# icom_interface.net
KiCad netlist of a schematic drawn in EAGLE
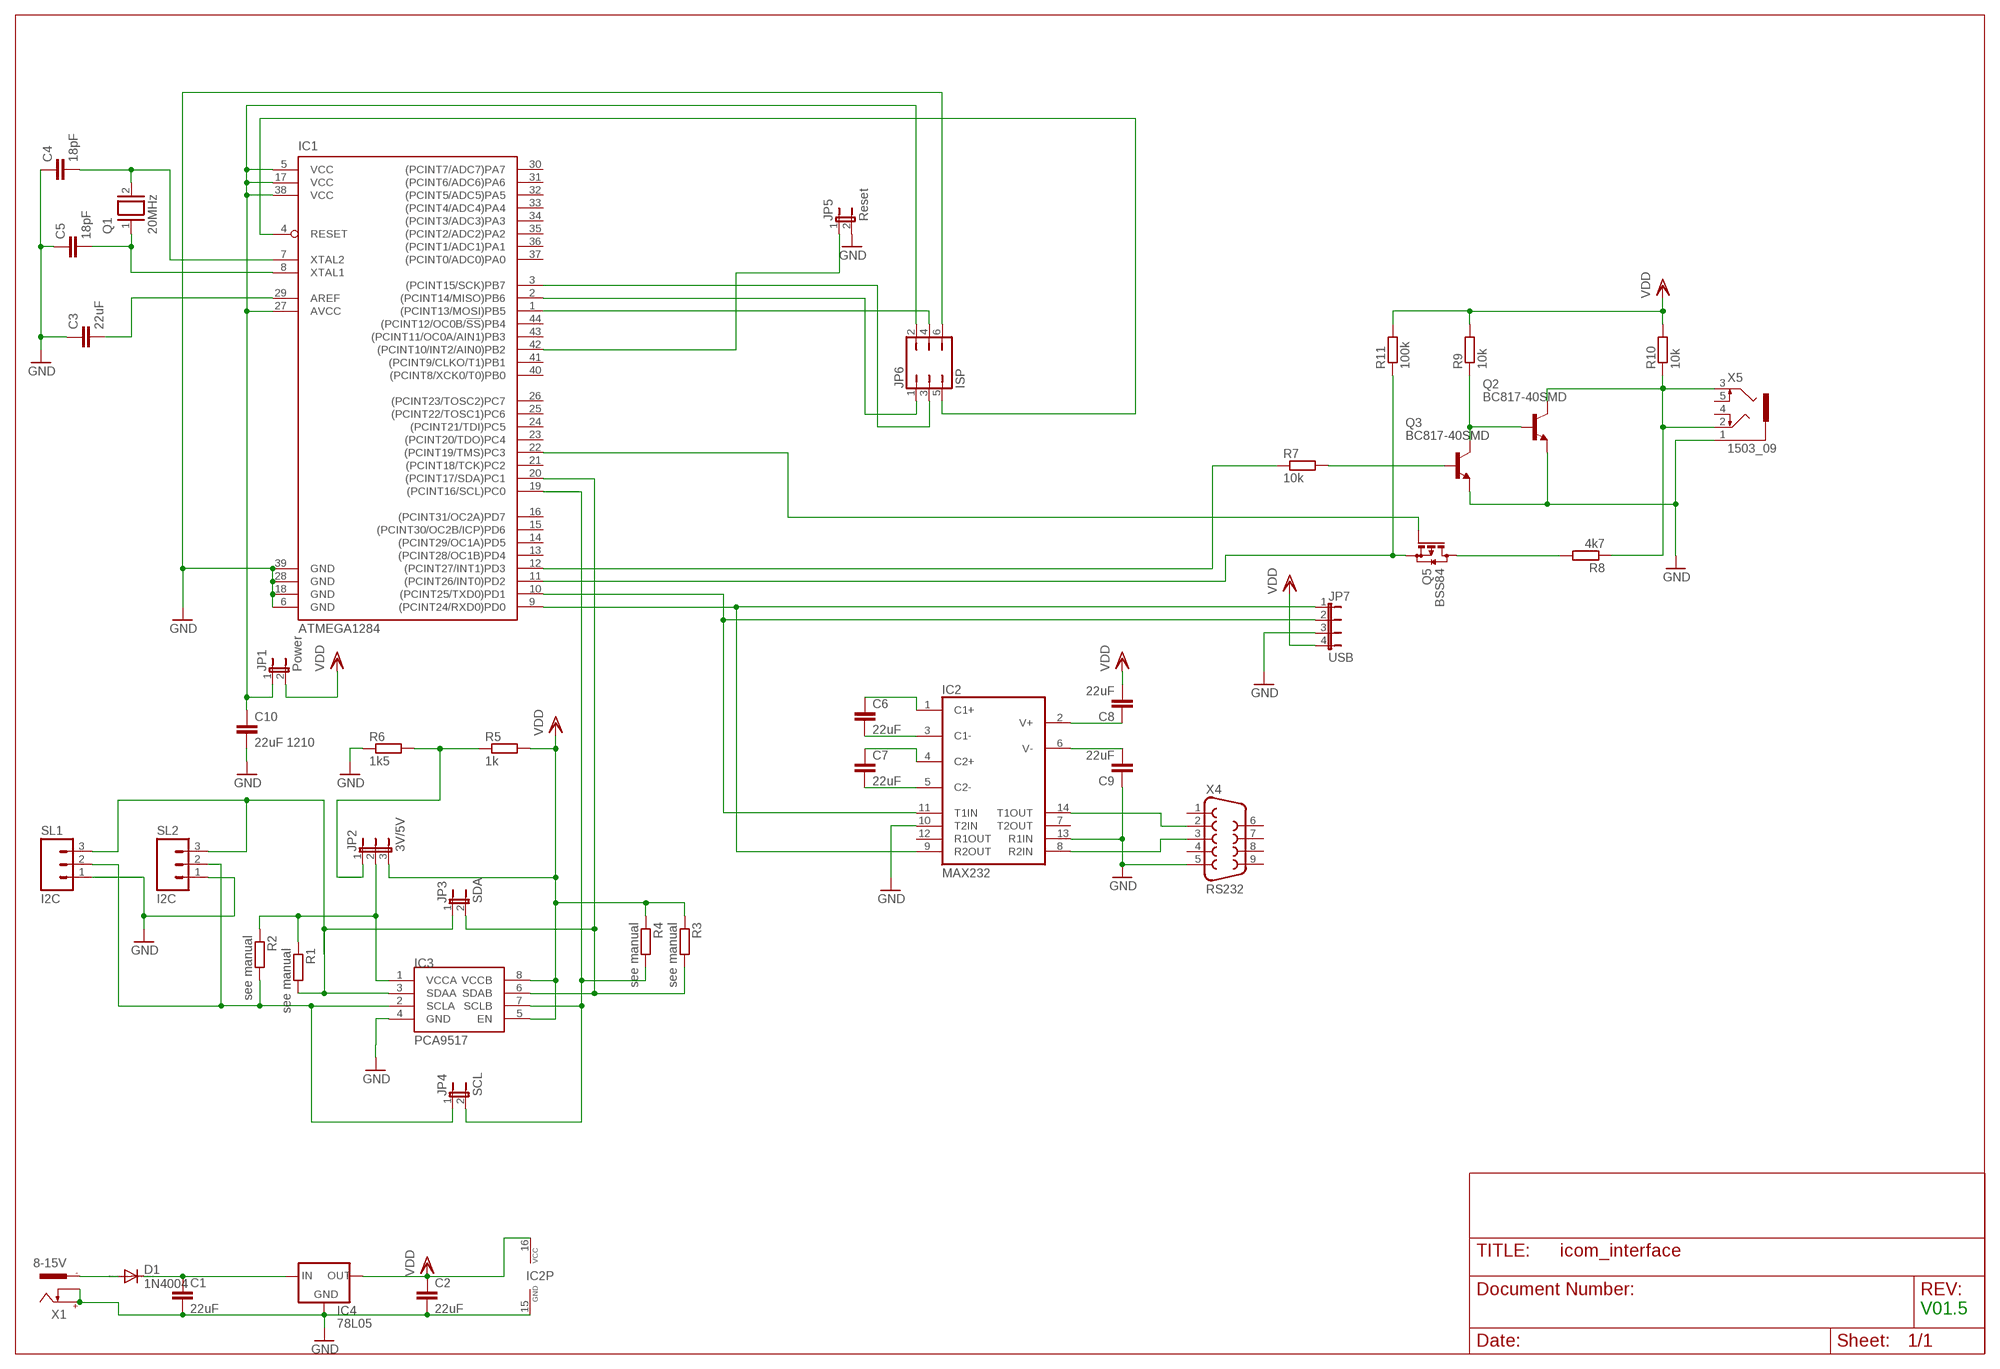
[diagram p0: schematic, sheet 1]

(export (version "E")
  (design (tool "Eeschema 10.0.6"))
  (components
    (comp (ref "C1")
      (value "22uF")
      (footprint "eagle-import:C1206")
      (libsource (lib "eagle-import") (part "C-EUC1206"))
    )
    (comp (ref "C2")
      (value "22uF")
      (footprint "eagle-import:C1206")
      (libsource (lib "eagle-import") (part "C-EUC1206"))
    )
    (comp (ref "C3")
      (value "22uF")
      (footprint "eagle-import:C1206")
      (libsource (lib "eagle-import") (part "C-EUC1206"))
    )
    (comp (ref "C4")
      (value "18pF")
      (footprint "eagle-import:C025-025X050")
      (libsource (lib "eagle-import") (part "resistor_C-EU025-025X050"))
    )
    (comp (ref "C5")
      (value "18pF")
      (footprint "eagle-import:C025-025X050")
      (libsource (lib "eagle-import") (part "resistor_C-EU025-025X050"))
    )
    (comp (ref "C6")
      (value "22uF")
      (footprint "eagle-import:C1206")
      (libsource (lib "eagle-import") (part "C-EUC1206"))
    )
    (comp (ref "C7")
      (value "22uF")
      (footprint "eagle-import:C1206")
      (libsource (lib "eagle-import") (part "C-EUC1206"))
    )
    (comp (ref "C8")
      (value "22uF")
      (footprint "eagle-import:C1206")
      (libsource (lib "eagle-import") (part "C-EUC1206"))
    )
    (comp (ref "C9")
      (value "22uF")
      (footprint "eagle-import:C1206")
      (libsource (lib "eagle-import") (part "C-EUC1206"))
    )
    (comp (ref "C10")
      (value "22uF 1210")
      (footprint "eagle-import:C1206")
      (libsource (lib "eagle-import") (part "C-EUC1206"))
    )
    (comp (ref "D1")
      (value "1N4004")
      (footprint "eagle-import:DO41-10")
      (libsource (lib "eagle-import") (part "1N4004"))
    )
    (comp (ref "IC1")
      (value "ATMEGA1284")
      (footprint "eagle-import:TQFP44")
      (fields (field (name "MPN") "ATMEGA644PV-10AU"))
      (libsource (lib "eagle-import") (part "ATMEGA644A"))
    )
    (comp (ref "IC2")
      (value "MAX232")
      (footprint "eagle-import:DIL16")
      (fields (field (name "MF") "MAXIM") (field (name "MPN") "MAX232ACPE+"))
      (libsource (lib "eagle-import") (part "MAX232"))
    )
    (comp (ref "IC3")
      (value "PCA9517")
      (footprint "eagle-import:SO-08")
      (libsource (lib "eagle-import") (part "PCA9517"))
    )
    (comp (ref "IC4")
      (value "78L05")
      (footprint "eagle-import:78LXX")
      (libsource (lib "eagle-import") (part "78LXX"))
    )
    (comp (ref "JP1")
      (value "Power")
      (footprint "eagle-import:JP1")
      (libsource (lib "eagle-import") (part "JP1E"))
    )
    (comp (ref "JP2")
      (value "3V/5V")
      (footprint "eagle-import:JP2")
      (libsource (lib "eagle-import") (part "JP2E"))
    )
    (comp (ref "JP3")
      (value "SDA")
      (footprint "eagle-import:JP1")
      (libsource (lib "eagle-import") (part "JP1E"))
    )
    (comp (ref "JP4")
      (value "SCL")
      (footprint "eagle-import:JP1")
      (libsource (lib "eagle-import") (part "JP1E"))
    )
    (comp (ref "JP5")
      (value "Reset")
      (footprint "eagle-import:JP1")
      (libsource (lib "eagle-import") (part "JP1E"))
    )
    (comp (ref "JP6")
      (value "ISP")
      (footprint "eagle-import:JP3Q")
      (libsource (lib "eagle-import") (part "JP3Q"))
    )
    (comp (ref "JP7")
      (value "USB")
      (footprint "eagle-import:JP4")
      (libsource (lib "eagle-import") (part "JP4E"))
    )
    (comp (ref "Q1")
      (value "20MHz")
      (footprint "eagle-import:QS")
      (libsource (lib "eagle-import") (part "XTAL/S"))
    )
    (comp (ref "Q2")
      (value "BC817-40SMD")
      (footprint "eagle-import:SOT23-BEC")
      (libsource (lib "eagle-import") (part "BC817SMD-40"))
    )
    (comp (ref "Q3")
      (value "BC817-40SMD")
      (footprint "eagle-import:SOT23-BEC")
      (libsource (lib "eagle-import") (part "BC817SMD-40"))
    )
    (comp (ref "Q5")
      (value "BSS84")
      (footprint "eagle-import:SOT23")
      (libsource (lib "eagle-import") (part "BSS84"))
    )
    (comp (ref "R1")
      (value "see manual")
      (footprint "eagle-import:R1206")
      (libsource (lib "eagle-import") (part "R-EU_R1206"))
    )
    (comp (ref "R2")
      (value "see manual")
      (footprint "eagle-import:R1206")
      (libsource (lib "eagle-import") (part "R-EU_R1206"))
    )
    (comp (ref "R3")
      (value "see manual")
      (footprint "eagle-import:R1206")
      (libsource (lib "eagle-import") (part "R-EU_R1206"))
    )
    (comp (ref "R4")
      (value "see manual")
      (footprint "eagle-import:R1206")
      (libsource (lib "eagle-import") (part "R-EU_R1206"))
    )
    (comp (ref "R5")
      (value "1k")
      (footprint "eagle-import:R1206")
      (libsource (lib "eagle-import") (part "R-EU_R1206"))
    )
    (comp (ref "R6")
      (value "1k5")
      (footprint "eagle-import:R1206")
      (libsource (lib "eagle-import") (part "R-EU_R1206"))
    )
    (comp (ref "R7")
      (value "10k")
      (footprint "eagle-import:R1206")
      (libsource (lib "eagle-import") (part "R-EU_R1206"))
    )
    (comp (ref "R8")
      (value "4k7")
      (footprint "eagle-import:R1206")
      (libsource (lib "eagle-import") (part "R-EU_R1206"))
    )
    (comp (ref "R9")
      (value "10k")
      (footprint "eagle-import:R1206")
      (libsource (lib "eagle-import") (part "R-EU_R1206"))
    )
    (comp (ref "R10")
      (value "10k")
      (footprint "eagle-import:R1206")
      (libsource (lib "eagle-import") (part "R-EU_R1206"))
    )
    (comp (ref "R11")
      (value "100k")
      (footprint "eagle-import:R1206")
      (libsource (lib "eagle-import") (part "R-EU_R1206"))
    )
    (comp (ref "SL1")
      (value "I2C")
      (footprint "eagle-import:03P")
      (libsource (lib "eagle-import") (part "M03"))
    )
    (comp (ref "SL2")
      (value "I2C")
      (footprint "eagle-import:03P")
      (libsource (lib "eagle-import") (part "M03"))
    )
    (comp (ref "X1")
      (value "8-15V")
      (footprint "eagle-import:737992-5")
      (libsource (lib "eagle-import") (part "737992-55"))
    )
    (comp (ref "X4")
      (value "RS232")
      (footprint "eagle-import:F09H")
      (libsource (lib "eagle-import") (part "F09H"))
    )
    (comp (ref "X5")
      (value "1503_09")
      (footprint "eagle-import:1503_09")
      (libsource (lib "eagle-import") (part "1503_09"))
    )
  )
  (nets
    (net (code "1") (name "GND") (class "Default")
      (node (ref "C1") (pin "2") (pinfunction "2_2") (pintype "passive"))
      (node (ref "C10") (pin "2") (pinfunction "2_2") (pintype "passive"))
      (node (ref "C2") (pin "2") (pinfunction "2_2") (pintype "passive"))
      (node (ref "C3") (pin "1") (pinfunction "1_1") (pintype "passive"))
      (node (ref "C4") (pin "1") (pinfunction "1_1") (pintype "passive"))
      (node (ref "C5") (pin "1") (pinfunction "1_1") (pintype "passive"))
      (node (ref "C9") (pin "1") (pinfunction "1_1") (pintype "passive"))
      (node (ref "IC1") (pin "18") (pinfunction "GND_18") (pintype "power_in"))
      (node (ref "IC1") (pin "28") (pinfunction "GND_28") (pintype "power_in"))
      (node (ref "IC1") (pin "39") (pinfunction "GND_39") (pintype "power_in"))
      (node (ref "IC1") (pin "6") (pinfunction "GND_6") (pintype "power_in"))
      (node (ref "IC2") (pin "10") (pinfunction "T2IN_10") (pintype "input"))
      (node (ref "IC2") (pin "13") (pinfunction "R1IN_13") (pintype "input"))
      (node (ref "IC2") (pin "15") (pinfunction "GND_15") (pintype "power_in"))
      (node (ref "IC3") (pin "4") (pinfunction "GND_4") (pintype "bidirectional"))
      (node (ref "IC4") (pin "GND") (pinfunction "GND_GND") (pintype "input"))
      (node (ref "JP5") (pin "2") (pinfunction "2_2") (pintype "passive"))
      (node (ref "JP6") (pin "6") (pinfunction "6_6") (pintype "passive"))
      (node (ref "JP7") (pin "3") (pinfunction "3_3") (pintype "passive"))
      (node (ref "Q2") (pin "E") (pinfunction "E_E") (pintype "passive"))
      (node (ref "Q3") (pin "E") (pinfunction "E_E") (pintype "passive"))
      (node (ref "R6") (pin "1") (pinfunction "1_1") (pintype "passive"))
      (node (ref "SL1") (pin "1") (pinfunction "1_1") (pintype "passive"))
      (node (ref "SL2") (pin "1") (pinfunction "1_1") (pintype "passive"))
      (node (ref "X1") (pin "+") (pinfunction "+_+") (pintype "passive"))
      (node (ref "X1") (pin "K") (pinfunction "K_K") (pintype "passive"))
      (node (ref "X4") (pin "5") (pinfunction "5_5") (pintype "passive"))
      (node (ref "X5") (pin "1") (pinfunction "1_1") (pintype "passive"))
    )
    (net (code "2") (name "Net-(C1-Pad1)") (class "Default")
      (node (ref "C1") (pin "1") (pinfunction "1_1") (pintype "passive"))
      (node (ref "D1") (pin "C") (pinfunction "C_C") (pintype "passive"))
      (node (ref "IC4") (pin "IN") (pinfunction "IN_IN") (pintype "input"))
    )
    (net (code "3") (name "Net-(D1-PadA)") (class "Default")
      (node (ref "D1") (pin "A") (pinfunction "A_A") (pintype "passive"))
      (node (ref "X1") (pin "-1") (pinfunction "-1_-1") (pintype "passive"))
    )
    (net (code "4") (name "Net-(IC1-(PCINT10{slash}INT2{slash}AIN0)PB2)") (class "Default")
      (node (ref "IC1") (pin "42") (pinfunction "(PCINT10/INT2/AIN0)PB2_42") (pintype "bidirectional"))
      (node (ref "JP5") (pin "1") (pinfunction "1_1") (pintype "passive"))
    )
    (net (code "5") (name "Net-(IC1-(PCINT13{slash}MOSI)PB5)") (class "Default")
      (node (ref "IC1") (pin "1") (pinfunction "(PCINT13/MOSI)PB5_1") (pintype "bidirectional"))
      (node (ref "JP6") (pin "4") (pinfunction "4_4") (pintype "passive"))
    )
    (net (code "6") (name "Net-(IC1-(PCINT14{slash}MISO)PB6)") (class "Default")
      (node (ref "IC1") (pin "2") (pinfunction "(PCINT14/MISO)PB6_2") (pintype "bidirectional"))
      (node (ref "JP6") (pin "1") (pinfunction "1_1") (pintype "passive"))
    )
    (net (code "7") (name "Net-(IC1-(PCINT15{slash}SCK)PB7)") (class "Default")
      (node (ref "IC1") (pin "3") (pinfunction "(PCINT15/SCK)PB7_3") (pintype "bidirectional"))
      (node (ref "JP6") (pin "3") (pinfunction "3_3") (pintype "passive"))
    )
    (net (code "8") (name "Net-(IC1-(PCINT16{slash}SCL)PC0)") (class "Default")
      (node (ref "IC1") (pin "19") (pinfunction "(PCINT16/SCL)PC0_19") (pintype "output"))
      (node (ref "IC3") (pin "7") (pinfunction "SCLB_7") (pintype "bidirectional"))
      (node (ref "JP4") (pin "2") (pinfunction "2_2") (pintype "passive"))
      (node (ref "R4") (pin "2") (pinfunction "2_2") (pintype "passive"))
    )
    (net (code "9") (name "Net-(IC1-(PCINT17{slash}SDA)PC1)") (class "Default")
      (node (ref "IC1") (pin "20") (pinfunction "(PCINT17/SDA)PC1_20") (pintype "output"))
      (node (ref "IC3") (pin "6") (pinfunction "SDAB_6") (pintype "bidirectional"))
      (node (ref "JP3") (pin "2") (pinfunction "2_2") (pintype "passive"))
      (node (ref "R3") (pin "2") (pinfunction "2_2") (pintype "passive"))
    )
    (net (code "10") (name "Net-(IC1-(PCINT19{slash}TMS)PC3)") (class "Default")
      (node (ref "IC1") (pin "22") (pinfunction "(PCINT19/TMS)PC3_22") (pintype "output"))
      (node (ref "Q5") (pin "1") (pinfunction "G_1") (pintype "passive"))
    )
    (net (code "11") (name "Net-(IC1-(PCINT24{slash}RXD0)PD0)") (class "Default")
      (node (ref "IC1") (pin "9") (pinfunction "(PCINT24/RXD0)PD0_9") (pintype "bidirectional"))
      (node (ref "IC2") (pin "9") (pinfunction "R2OUT_9") (pintype "output"))
      (node (ref "JP7") (pin "1") (pinfunction "1_1") (pintype "passive"))
    )
    (net (code "12") (name "Net-(IC1-(PCINT25{slash}TXD0)PD1)") (class "Default")
      (node (ref "IC1") (pin "10") (pinfunction "(PCINT25/TXD0)PD1_10") (pintype "bidirectional"))
      (node (ref "IC2") (pin "11") (pinfunction "T1IN_11") (pintype "input"))
      (node (ref "JP7") (pin "2") (pinfunction "2_2") (pintype "passive"))
    )
    (net (code "13") (name "Net-(IC1-(PCINT26{slash}INT0)PD2)") (class "Default")
      (node (ref "IC1") (pin "11") (pinfunction "(PCINT26/INT0)PD2_11") (pintype "bidirectional"))
      (node (ref "Q5") (pin "2") (pinfunction "S_2") (pintype "passive"))
      (node (ref "R11") (pin "1") (pinfunction "1_1") (pintype "passive"))
    )
    (net (code "14") (name "Net-(IC1-(PCINT27{slash}INT1)PD3)") (class "Default")
      (node (ref "IC1") (pin "12") (pinfunction "(PCINT27/INT1)PD3_12") (pintype "bidirectional"))
      (node (ref "R7") (pin "1") (pinfunction "1_1") (pintype "passive"))
    )
    (net (code "15") (name "Net-(IC1-AREF)") (class "Default")
      (node (ref "C3") (pin "2") (pinfunction "2_2") (pintype "passive"))
      (node (ref "IC1") (pin "29") (pinfunction "AREF_29") (pintype "passive"))
    )
    (net (code "16") (name "Net-(IC1-AVCC)") (class "Default")
      (node (ref "C10") (pin "1") (pinfunction "1_1") (pintype "passive"))
      (node (ref "IC1") (pin "17") (pinfunction "VCC_17") (pintype "power_in"))
      (node (ref "IC1") (pin "27") (pinfunction "AVCC_27") (pintype "power_in"))
      (node (ref "IC1") (pin "38") (pinfunction "VCC_38") (pintype "power_in"))
      (node (ref "IC1") (pin "5") (pinfunction "VCC_5") (pintype "power_in"))
      (node (ref "JP1") (pin "1") (pinfunction "1_1") (pintype "passive"))
      (node (ref "JP6") (pin "2") (pinfunction "2_2") (pintype "passive"))
    )
    (net (code "17") (name "Net-(IC1-RESET)") (class "Default")
      (node (ref "IC1") (pin "4") (pinfunction "RESET_4") (pintype "input"))
      (node (ref "JP6") (pin "5") (pinfunction "5_5") (pintype "passive"))
    )
    (net (code "18") (name "Net-(IC1-XTAL1)") (class "Default")
      (node (ref "C5") (pin "2") (pinfunction "2_2") (pintype "passive"))
      (node (ref "IC1") (pin "8") (pinfunction "XTAL1_8") (pintype "bidirectional"))
      (node (ref "Q1") (pin "1") (pinfunction "1_1") (pintype "passive"))
    )
    (net (code "19") (name "Net-(IC1-XTAL2)") (class "Default")
      (node (ref "C4") (pin "2") (pinfunction "2_2") (pintype "passive"))
      (node (ref "IC1") (pin "7") (pinfunction "XTAL2_7") (pintype "bidirectional"))
      (node (ref "Q1") (pin "2") (pinfunction "2_2") (pintype "passive"))
    )
    (net (code "20") (name "Net-(IC2A-C1+)") (class "Default")
      (node (ref "C6") (pin "1") (pinfunction "1_1") (pintype "passive"))
      (node (ref "IC2") (pin "1") (pinfunction "C1+_1") (pintype "bidirectional"))
    )
    (net (code "21") (name "Net-(IC2A-C1-)") (class "Default")
      (node (ref "C6") (pin "2") (pinfunction "2_2") (pintype "passive"))
      (node (ref "IC2") (pin "3") (pinfunction "C1-_3") (pintype "bidirectional"))
    )
    (net (code "22") (name "Net-(IC2A-C2+)") (class "Default")
      (node (ref "C7") (pin "1") (pinfunction "1_1") (pintype "passive"))
      (node (ref "IC2") (pin "4") (pinfunction "C2+_4") (pintype "bidirectional"))
    )
    (net (code "23") (name "Net-(IC2A-C2-)") (class "Default")
      (node (ref "C7") (pin "2") (pinfunction "2_2") (pintype "passive"))
      (node (ref "IC2") (pin "5") (pinfunction "C2-_5") (pintype "bidirectional"))
    )
    (net (code "24") (name "Net-(IC2A-R2IN)") (class "Default")
      (node (ref "IC2") (pin "8") (pinfunction "R2IN_8") (pintype "input"))
      (node (ref "X4") (pin "3") (pinfunction "3_3") (pintype "passive"))
    )
    (net (code "25") (name "Net-(IC2A-T1OUT)") (class "Default")
      (node (ref "IC2") (pin "14") (pinfunction "T1OUT_14") (pintype "output"))
      (node (ref "X4") (pin "2") (pinfunction "2_2") (pintype "passive"))
    )
    (net (code "26") (name "Net-(IC2A-V+)") (class "Default")
      (node (ref "C8") (pin "1") (pinfunction "1_1") (pintype "passive"))
      (node (ref "IC2") (pin "2") (pinfunction "V+_2") (pintype "bidirectional"))
    )
    (net (code "27") (name "Net-(IC2A-V-)") (class "Default")
      (node (ref "C9") (pin "2") (pinfunction "2_2") (pintype "passive"))
      (node (ref "IC2") (pin "6") (pinfunction "V-_6") (pintype "bidirectional"))
    )
    (net (code "28") (name "Net-(IC3-SCLA)") (class "Default")
      (node (ref "IC3") (pin "2") (pinfunction "SCLA_2") (pintype "bidirectional"))
      (node (ref "JP4") (pin "1") (pinfunction "1_1") (pintype "passive"))
      (node (ref "R2") (pin "2") (pinfunction "2_2") (pintype "passive"))
      (node (ref "SL1") (pin "2") (pinfunction "2_2") (pintype "passive"))
      (node (ref "SL2") (pin "2") (pinfunction "2_2") (pintype "passive"))
    )
    (net (code "29") (name "Net-(IC3-SDAA)") (class "Default")
      (node (ref "IC3") (pin "3") (pinfunction "SDAA_3") (pintype "bidirectional"))
      (node (ref "JP3") (pin "1") (pinfunction "1_1") (pintype "passive"))
      (node (ref "R1") (pin "2") (pinfunction "2_2") (pintype "passive"))
      (node (ref "SL1") (pin "3") (pinfunction "3_3") (pintype "passive"))
      (node (ref "SL2") (pin "3") (pinfunction "3_3") (pintype "passive"))
    )
    (net (code "30") (name "Net-(IC3-VCCA)") (class "Default")
      (node (ref "IC3") (pin "1") (pinfunction "VCCA_1") (pintype "bidirectional"))
      (node (ref "JP2") (pin "2") (pinfunction "2_2") (pintype "passive"))
      (node (ref "R1") (pin "1") (pinfunction "1_1") (pintype "passive"))
      (node (ref "R2") (pin "1") (pinfunction "1_1") (pintype "passive"))
    )
    (net (code "31") (name "Net-(JP2-Pad1)") (class "Default")
      (node (ref "JP2") (pin "1") (pinfunction "1_1") (pintype "passive"))
      (node (ref "R5") (pin "1") (pinfunction "1_1") (pintype "passive"))
      (node (ref "R6") (pin "2") (pinfunction "2_2") (pintype "passive"))
    )
    (net (code "32") (name "Net-(Q2-PadB)") (class "Default")
      (node (ref "Q2") (pin "B") (pinfunction "B_B") (pintype "passive"))
      (node (ref "Q3") (pin "C") (pinfunction "C_C") (pintype "passive"))
      (node (ref "R9") (pin "1") (pinfunction "1_1") (pintype "passive"))
    )
    (net (code "33") (name "Net-(Q2-PadC)") (class "Default")
      (node (ref "Q2") (pin "C") (pinfunction "C_C") (pintype "passive"))
      (node (ref "R10") (pin "1") (pinfunction "1_1") (pintype "passive"))
      (node (ref "R8") (pin "1") (pinfunction "1_1") (pintype "passive"))
      (node (ref "X5") (pin "2") (pinfunction "2_2") (pintype "passive"))
      (node (ref "X5") (pin "3") (pinfunction "3_3") (pintype "passive"))
    )
    (net (code "34") (name "Net-(Q3-PadB)") (class "Default")
      (node (ref "Q3") (pin "B") (pinfunction "B_B") (pintype "passive"))
      (node (ref "R7") (pin "2") (pinfunction "2_2") (pintype "passive"))
    )
    (net (code "35") (name "Net-(Q5-D)") (class "Default")
      (node (ref "Q5") (pin "3") (pinfunction "D_3") (pintype "passive"))
      (node (ref "R8") (pin "2") (pinfunction "2_2") (pintype "passive"))
    )
    (net (code "36") (name "VDD") (class "Default")
      (node (ref "C2") (pin "1") (pinfunction "1_1") (pintype "passive"))
      (node (ref "C8") (pin "2") (pinfunction "2_2") (pintype "passive"))
      (node (ref "IC2") (pin "16") (pinfunction "VCC_16") (pintype "power_in"))
      (node (ref "IC3") (pin "5") (pinfunction "EN_5") (pintype "bidirectional"))
      (node (ref "IC3") (pin "8") (pinfunction "VCCB_8") (pintype "bidirectional"))
      (node (ref "IC4") (pin "OUT") (pinfunction "OUT_OUT") (pintype "passive"))
      (node (ref "JP1") (pin "2") (pinfunction "2_2") (pintype "passive"))
      (node (ref "JP2") (pin "3") (pinfunction "3_3") (pintype "passive"))
      (node (ref "JP7") (pin "4") (pinfunction "4_4") (pintype "passive"))
      (node (ref "R10") (pin "2") (pinfunction "2_2") (pintype "passive"))
      (node (ref "R11") (pin "2") (pinfunction "2_2") (pintype "passive"))
      (node (ref "R3") (pin "1") (pinfunction "1_1") (pintype "passive"))
      (node (ref "R4") (pin "1") (pinfunction "1_1") (pintype "passive"))
      (node (ref "R5") (pin "2") (pinfunction "2_2") (pintype "passive"))
      (node (ref "R9") (pin "2") (pinfunction "2_2") (pintype "passive"))
    )
    (net (code "37") (name "unconnected-(IC1-(PCINT0{slash}ADC0)PA0-Pad37)") (class "Default")
      (node (ref "IC1") (pin "37") (pinfunction "(PCINT0/ADC0)PA0_37") (pintype "bidirectional"))
    )
    (net (code "38") (name "unconnected-(IC1-(PCINT1{slash}ADC1)PA1-Pad36)") (class "Default")
      (node (ref "IC1") (pin "36") (pinfunction "(PCINT1/ADC1)PA1_36") (pintype "bidirectional"))
    )
    (net (code "39") (name "unconnected-(IC1-(PCINT2{slash}ADC2)PA2-Pad35)") (class "Default")
      (node (ref "IC1") (pin "35") (pinfunction "(PCINT2/ADC2)PA2_35") (pintype "bidirectional"))
    )
    (net (code "40") (name "unconnected-(IC1-(PCINT3{slash}ADC3)PA3-Pad34)") (class "Default")
      (node (ref "IC1") (pin "34") (pinfunction "(PCINT3/ADC3)PA3_34") (pintype "bidirectional"))
    )
    (net (code "41") (name "unconnected-(IC1-(PCINT4{slash}ADC4)PA4-Pad33)") (class "Default")
      (node (ref "IC1") (pin "33") (pinfunction "(PCINT4/ADC4)PA4_33") (pintype "bidirectional"))
    )
    (net (code "42") (name "unconnected-(IC1-(PCINT5{slash}ADC5)PA5-Pad32)") (class "Default")
      (node (ref "IC1") (pin "32") (pinfunction "(PCINT5/ADC5)PA5_32") (pintype "bidirectional"))
    )
    (net (code "43") (name "unconnected-(IC1-(PCINT6{slash}ADC6)PA6-Pad31)") (class "Default")
      (node (ref "IC1") (pin "31") (pinfunction "(PCINT6/ADC6)PA6_31") (pintype "bidirectional"))
    )
    (net (code "44") (name "unconnected-(IC1-(PCINT7{slash}ADC7)PA7-Pad30)") (class "Default")
      (node (ref "IC1") (pin "30") (pinfunction "(PCINT7/ADC7)PA7_30") (pintype "bidirectional"))
    )
    (net (code "45") (name "unconnected-(IC1-(PCINT8{slash}XCK0{slash}T0)PB0-Pad40)") (class "Default")
      (node (ref "IC1") (pin "40") (pinfunction "(PCINT8/XCK0/T0)PB0_40") (pintype "bidirectional"))
    )
    (net (code "46") (name "unconnected-(IC1-(PCINT9{slash}CLKO{slash}T1)PB1-Pad41)") (class "Default")
      (node (ref "IC1") (pin "41") (pinfunction "(PCINT9/CLKO/T1)PB1_41") (pintype "bidirectional"))
    )
    (net (code "47") (name "unconnected-(IC1-(PCINT11{slash}OC0A{slash}AIN1)PB3-Pad43)") (class "Default")
      (node (ref "IC1") (pin "43") (pinfunction "(PCINT11/OC0A/AIN1)PB3_43") (pintype "bidirectional"))
    )
    (net (code "48") (name "unconnected-(IC1-(PCINT12{slash}OC0B{slash}~{SS})PB4-Pad44)") (class "Default")
      (node (ref "IC1") (pin "44") (pinfunction "(PCINT12/OC0B/~{SS})PB4_44") (pintype "bidirectional"))
    )
    (net (code "49") (name "unconnected-(IC1-(PCINT18{slash}TCK)PC2-Pad21)") (class "Default")
      (node (ref "IC1") (pin "21") (pinfunction "(PCINT18/TCK)PC2_21") (pintype "output"))
    )
    (net (code "50") (name "unconnected-(IC1-(PCINT20{slash}TDO)PC4-Pad23)") (class "Default")
      (node (ref "IC1") (pin "23") (pinfunction "(PCINT20/TDO)PC4_23") (pintype "output"))
    )
    (net (code "51") (name "unconnected-(IC1-(PCINT21{slash}TDI)PC5-Pad24)") (class "Default")
      (node (ref "IC1") (pin "24") (pinfunction "(PCINT21/TDI)PC5_24") (pintype "output"))
    )
    (net (code "52") (name "unconnected-(IC1-(PCINT22{slash}TOSC1)PC6-Pad25)") (class "Default")
      (node (ref "IC1") (pin "25") (pinfunction "(PCINT22/TOSC1)PC6_25") (pintype "output"))
    )
    (net (code "53") (name "unconnected-(IC1-(PCINT23{slash}TOSC2)PC7-Pad26)") (class "Default")
      (node (ref "IC1") (pin "26") (pinfunction "(PCINT23/TOSC2)PC7_26") (pintype "output"))
    )
    (net (code "54") (name "unconnected-(IC1-(PCINT28{slash}OC1B)PD4-Pad13)") (class "Default")
      (node (ref "IC1") (pin "13") (pinfunction "(PCINT28/OC1B)PD4_13") (pintype "bidirectional"))
    )
    (net (code "55") (name "unconnected-(IC1-(PCINT29{slash}OC1A)PD5-Pad14)") (class "Default")
      (node (ref "IC1") (pin "14") (pinfunction "(PCINT29/OC1A)PD5_14") (pintype "bidirectional"))
    )
    (net (code "56") (name "unconnected-(IC1-(PCINT30{slash}OC2B{slash}ICP)PD6-Pad15)") (class "Default")
      (node (ref "IC1") (pin "15") (pinfunction "(PCINT30/OC2B/ICP)PD6_15") (pintype "bidirectional"))
    )
    (net (code "57") (name "unconnected-(IC1-(PCINT31{slash}OC2A)PD7-Pad16)") (class "Default")
      (node (ref "IC1") (pin "16") (pinfunction "(PCINT31/OC2A)PD7_16") (pintype "bidirectional"))
    )
    (net (code "58") (name "unconnected-(IC2A-R1OUT-Pad12)") (class "Default")
      (node (ref "IC2") (pin "12") (pinfunction "R1OUT_12") (pintype "output"))
    )
    (net (code "59") (name "unconnected-(IC2A-T2OUT-Pad7)") (class "Default")
      (node (ref "IC2") (pin "7") (pinfunction "T2OUT_7") (pintype "output"))
    )
    (net (code "60") (name "unconnected-(X1-Pad-2)") (class "Default")
      (node (ref "X1") (pin "-2") (pinfunction "-2_-2") (pintype "passive"))
    )
    (net (code "61") (name "unconnected-(X4-Pad1)") (class "Default")
      (node (ref "X4") (pin "1") (pinfunction "1_1") (pintype "passive"))
    )
    (net (code "62") (name "unconnected-(X4-Pad4)") (class "Default")
      (node (ref "X4") (pin "4") (pinfunction "4_4") (pintype "passive"))
    )
    (net (code "63") (name "unconnected-(X4-Pad6)") (class "Default")
      (node (ref "X4") (pin "6") (pinfunction "6_6") (pintype "passive"))
    )
    (net (code "64") (name "unconnected-(X4-Pad7)") (class "Default")
      (node (ref "X4") (pin "7") (pinfunction "7_7") (pintype "passive"))
    )
    (net (code "65") (name "unconnected-(X4-Pad8)") (class "Default")
      (node (ref "X4") (pin "8") (pinfunction "8_8") (pintype "passive"))
    )
    (net (code "66") (name "unconnected-(X4-Pad9)") (class "Default")
      (node (ref "X4") (pin "9") (pinfunction "9_9") (pintype "passive"))
    )
    (net (code "67") (name "unconnected-(X5-Pad4)") (class "Default")
      (node (ref "X5") (pin "4") (pinfunction "4_4") (pintype "passive"))
    )
    (net (code "68") (name "unconnected-(X5-Pad5)") (class "Default")
      (node (ref "X5") (pin "5") (pinfunction "5_5") (pintype "passive"))
    )
  )
)
